# sensores.net
KiCad netlist of a schematic drawn in Altium Designer
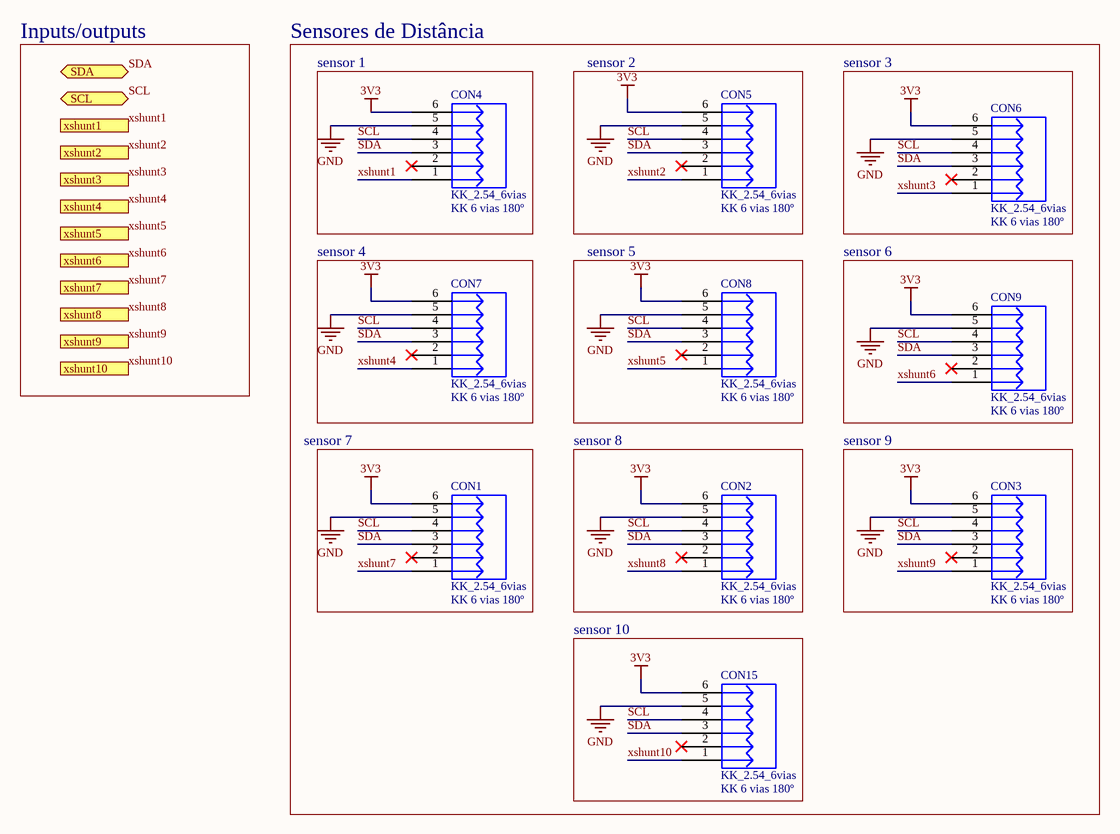
[diagram p0: sensores.SchDoc]

(export (version "E")
  (design (tool "Eeschema 10.0.6"))
  (components
    (comp (ref "CON1")
      (value "KK_2.54_6vias")
      (footprint "KK_6vias_180°")
      (description "Conector KK 2.54mm 6 vias")
      (fields (field (name "VALOR") "KK 6 vias 180º"))
      (libsource (lib "Conectores_Sch") (part "KK_2.54_6vias"))
    )
    (comp (ref "CON2")
      (value "KK_2.54_6vias")
      (footprint "KK_6vias_180°")
      (description "Conector KK 2.54mm 6 vias")
      (fields (field (name "VALOR") "KK 6 vias 180º"))
      (libsource (lib "Conectores_Sch") (part "KK_2.54_6vias"))
    )
    (comp (ref "CON3")
      (value "KK_2.54_6vias")
      (footprint "KK_6vias_180°")
      (description "Conector KK 2.54mm 6 vias")
      (fields (field (name "VALOR") "KK 6 vias 180º"))
      (libsource (lib "Conectores_Sch") (part "KK_2.54_6vias"))
    )
    (comp (ref "CON4")
      (value "KK_2.54_6vias")
      (footprint "KK_6vias_180°")
      (description "Conector KK 2.54mm 6 vias")
      (fields (field (name "VALOR") "KK 6 vias 180º"))
      (libsource (lib "Conectores_Sch") (part "KK_2.54_6vias"))
    )
    (comp (ref "CON5")
      (value "KK_2.54_6vias")
      (footprint "KK_6vias_180°")
      (description "Conector KK 2.54mm 6 vias")
      (fields (field (name "VALOR") "KK 6 vias 180º"))
      (libsource (lib "Conectores_Sch") (part "KK_2.54_6vias"))
    )
    (comp (ref "CON6")
      (value "KK_2.54_6vias")
      (footprint "KK_6vias_180°")
      (description "Conector KK 2.54mm 6 vias")
      (fields (field (name "VALOR") "KK 6 vias 180º"))
      (libsource (lib "Conectores_Sch") (part "KK_2.54_6vias"))
    )
    (comp (ref "CON7")
      (value "KK_2.54_6vias")
      (footprint "KK_6vias_180°")
      (description "Conector KK 2.54mm 6 vias")
      (fields (field (name "VALOR") "KK 6 vias 180º"))
      (libsource (lib "Conectores_Sch") (part "KK_2.54_6vias"))
    )
    (comp (ref "CON8")
      (value "KK_2.54_6vias")
      (footprint "KK_6vias_180°")
      (description "Conector KK 2.54mm 6 vias")
      (fields (field (name "VALOR") "KK 6 vias 180º"))
      (libsource (lib "Conectores_Sch") (part "KK_2.54_6vias"))
    )
    (comp (ref "CON9")
      (value "KK_2.54_6vias")
      (footprint "KK_6vias_180°")
      (description "Conector KK 2.54mm 6 vias")
      (fields (field (name "VALOR") "KK 6 vias 180º"))
      (libsource (lib "Conectores_Sch") (part "KK_2.54_6vias"))
    )
    (comp (ref "CON15")
      (value "KK_2.54_6vias")
      (footprint "KK_6vias_180°")
      (description "Conector KK 2.54mm 6 vias")
      (fields (field (name "VALOR") "KK 6 vias 180º"))
      (libsource (lib "Conectores_Sch") (part "KK_2.54_6vias"))
    )
  )
  (nets
    (net (code "1") (name "/SCL") (class "Default")
      (node (ref "CON1") (pin "4") (pintype "passive"))
      (node (ref "CON15") (pin "4") (pintype "passive"))
      (node (ref "CON2") (pin "4") (pintype "passive"))
      (node (ref "CON3") (pin "4") (pintype "passive"))
      (node (ref "CON4") (pin "4") (pintype "passive"))
      (node (ref "CON5") (pin "4") (pintype "passive"))
      (node (ref "CON6") (pin "4") (pintype "passive"))
      (node (ref "CON7") (pin "4") (pintype "passive"))
      (node (ref "CON8") (pin "4") (pintype "passive"))
      (node (ref "CON9") (pin "4") (pintype "passive"))
    )
    (net (code "2") (name "/SDA") (class "Default")
      (node (ref "CON1") (pin "3") (pintype "passive"))
      (node (ref "CON15") (pin "3") (pintype "passive"))
      (node (ref "CON2") (pin "3") (pintype "passive"))
      (node (ref "CON3") (pin "3") (pintype "passive"))
      (node (ref "CON4") (pin "3") (pintype "passive"))
      (node (ref "CON5") (pin "3") (pintype "passive"))
      (node (ref "CON6") (pin "3") (pintype "passive"))
      (node (ref "CON7") (pin "3") (pintype "passive"))
      (node (ref "CON8") (pin "3") (pintype "passive"))
      (node (ref "CON9") (pin "3") (pintype "passive"))
    )
    (net (code "3") (name "/xshunt1") (class "Default") (node (ref "CON4") (pin "1") (pintype "passive")))
    (net (code "4") (name "/xshunt2") (class "Default") (node (ref "CON5") (pin "1") (pintype "passive")))
    (net (code "5") (name "/xshunt3") (class "Default") (node (ref "CON6") (pin "1") (pintype "passive")))
    (net (code "6") (name "/xshunt4") (class "Default") (node (ref "CON7") (pin "1") (pintype "passive")))
    (net (code "7") (name "/xshunt5") (class "Default") (node (ref "CON8") (pin "1") (pintype "passive")))
    (net (code "8") (name "/xshunt6") (class "Default") (node (ref "CON9") (pin "1") (pintype "passive")))
    (net (code "9") (name "/xshunt7") (class "Default") (node (ref "CON1") (pin "1") (pintype "passive")))
    (net (code "10") (name "/xshunt8") (class "Default") (node (ref "CON2") (pin "1") (pintype "passive")))
    (net (code "11") (name "/xshunt9") (class "Default") (node (ref "CON3") (pin "1") (pintype "passive")))
    (net (code "12") (name "/xshunt10") (class "Default") (node (ref "CON15") (pin "1") (pintype "passive")))
    (net (code "13") (name "3V3") (class "Default")
      (node (ref "CON1") (pin "6") (pintype "passive"))
      (node (ref "CON15") (pin "6") (pintype "passive"))
      (node (ref "CON2") (pin "6") (pintype "passive"))
      (node (ref "CON3") (pin "6") (pintype "passive"))
      (node (ref "CON4") (pin "6") (pintype "passive"))
      (node (ref "CON5") (pin "6") (pintype "passive"))
      (node (ref "CON6") (pin "6") (pintype "passive"))
      (node (ref "CON7") (pin "6") (pintype "passive"))
      (node (ref "CON8") (pin "6") (pintype "passive"))
      (node (ref "CON9") (pin "6") (pintype "passive"))
    )
    (net (code "14") (name "GND") (class "Default")
      (node (ref "CON1") (pin "5") (pintype "passive"))
      (node (ref "CON15") (pin "5") (pintype "passive"))
      (node (ref "CON2") (pin "5") (pintype "passive"))
      (node (ref "CON3") (pin "5") (pintype "passive"))
      (node (ref "CON4") (pin "5") (pintype "passive"))
      (node (ref "CON5") (pin "5") (pintype "passive"))
      (node (ref "CON6") (pin "5") (pintype "passive"))
      (node (ref "CON7") (pin "5") (pintype "passive"))
      (node (ref "CON8") (pin "5") (pintype "passive"))
      (node (ref "CON9") (pin "5") (pintype "passive"))
    )
    (net (code "15") (name "unconnected-(CON1-Pad2)") (class "Default")
      (node (ref "CON1") (pin "2") (pintype "passive+no_connect"))
    )
    (net (code "16") (name "unconnected-(CON2-Pad2)") (class "Default")
      (node (ref "CON2") (pin "2") (pintype "passive+no_connect"))
    )
    (net (code "17") (name "unconnected-(CON3-Pad2)") (class "Default")
      (node (ref "CON3") (pin "2") (pintype "passive+no_connect"))
    )
    (net (code "18") (name "unconnected-(CON4-Pad2)") (class "Default")
      (node (ref "CON4") (pin "2") (pintype "passive+no_connect"))
    )
    (net (code "19") (name "unconnected-(CON5-Pad2)") (class "Default")
      (node (ref "CON5") (pin "2") (pintype "passive+no_connect"))
    )
    (net (code "20") (name "unconnected-(CON6-Pad2)") (class "Default")
      (node (ref "CON6") (pin "2") (pintype "passive+no_connect"))
    )
    (net (code "21") (name "unconnected-(CON7-Pad2)") (class "Default")
      (node (ref "CON7") (pin "2") (pintype "passive+no_connect"))
    )
    (net (code "22") (name "unconnected-(CON8-Pad2)") (class "Default")
      (node (ref "CON8") (pin "2") (pintype "passive+no_connect"))
    )
    (net (code "23") (name "unconnected-(CON9-Pad2)") (class "Default")
      (node (ref "CON9") (pin "2") (pintype "passive+no_connect"))
    )
    (net (code "24") (name "unconnected-(CON15-Pad2)") (class "Default")
      (node (ref "CON15") (pin "2") (pintype "passive+no_connect"))
    )
  )
)
